# W705A.net
KiCad netlist of a schematic drawn in EAGLE
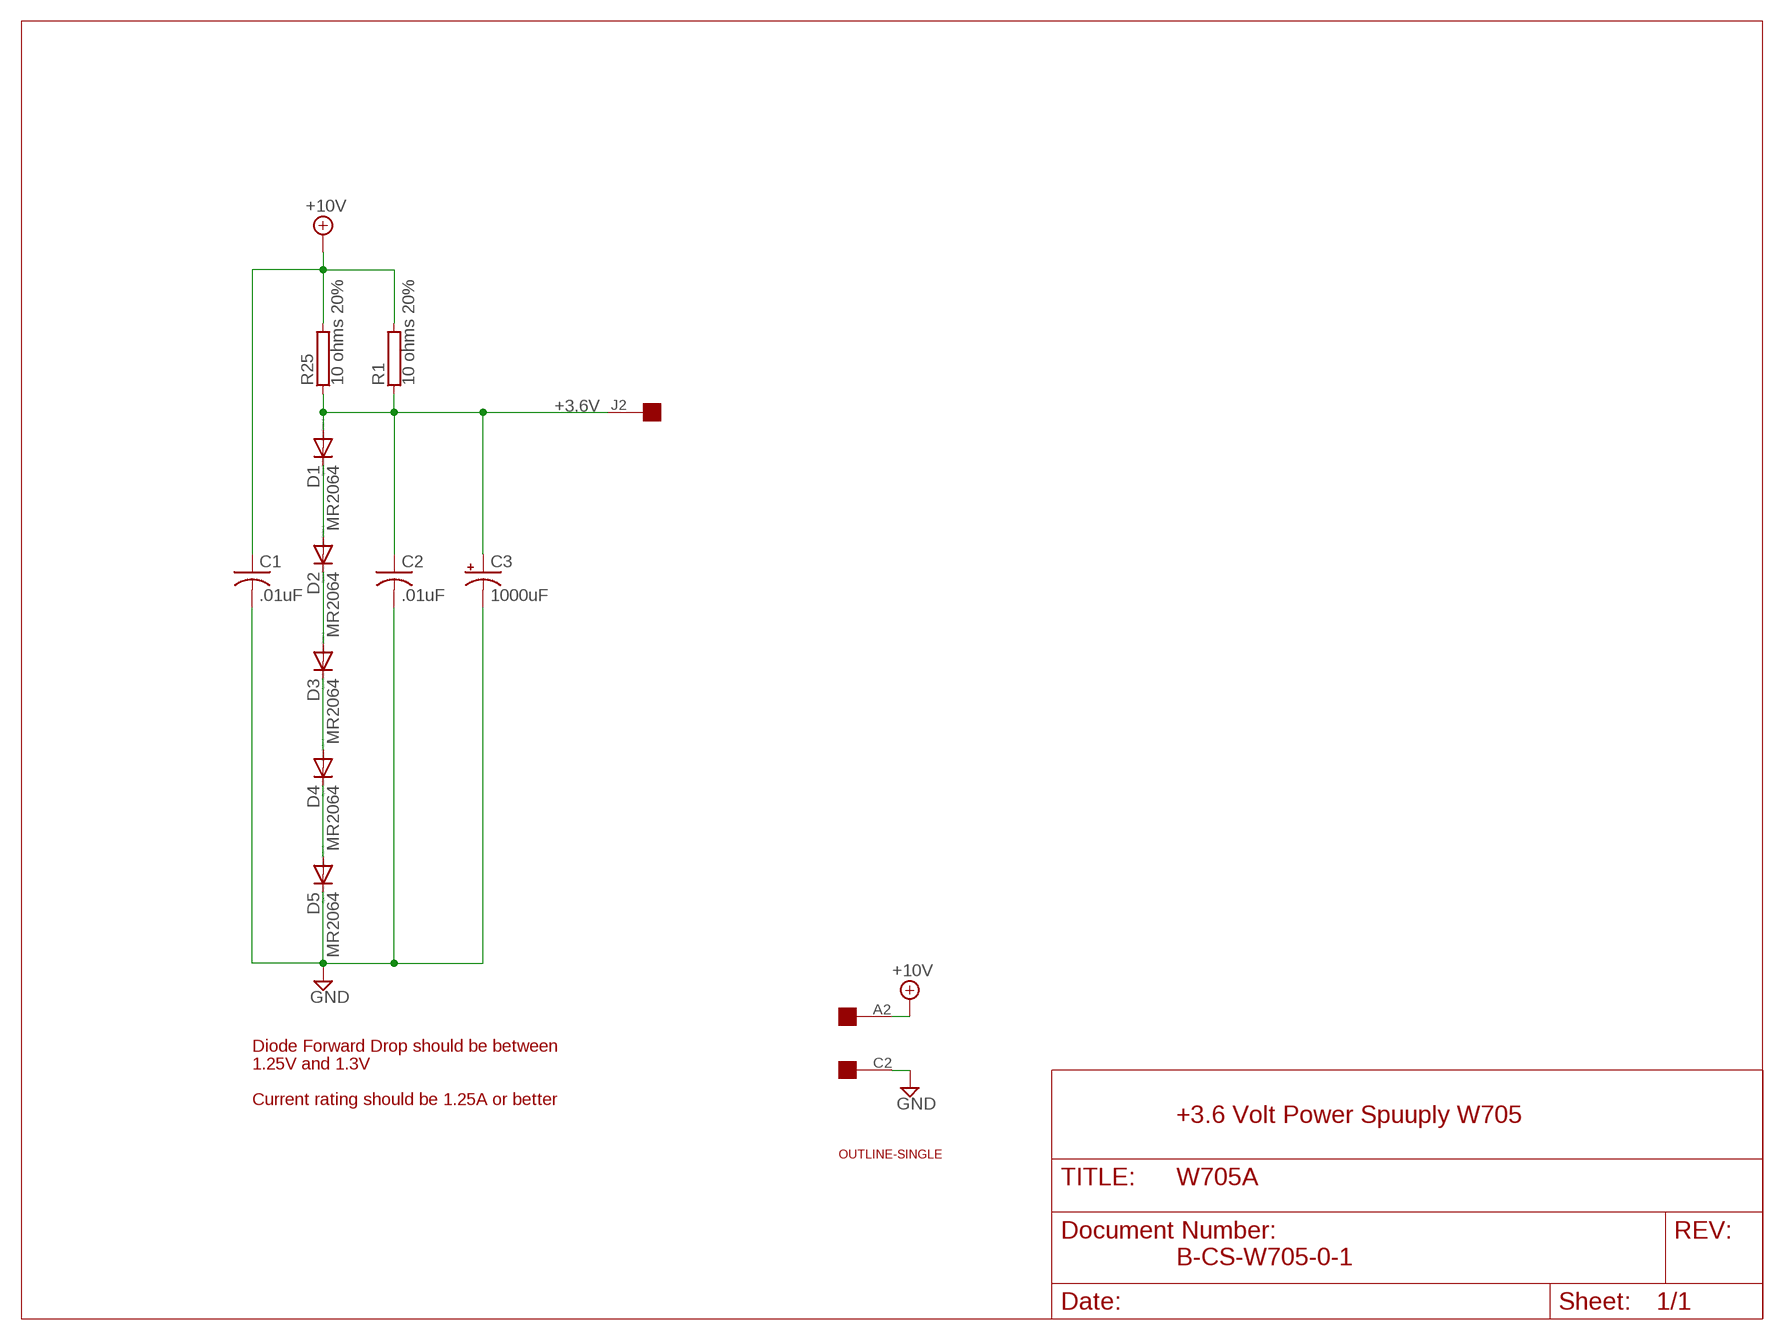
[diagram p0: schematic, sheet 1]

(export (version "E")
  (design (tool "Eeschema 10.0.6"))
  (components
    (comp (ref "C1")
      (value ".01uF")
      (footprint "eagle-import:C050-025X075")
      (libsource (lib "eagle-import") (part "C-US050-025X075"))
    )
    (comp (ref "C2")
      (value ".01uF")
      (footprint "eagle-import:C050-025X075")
      (libsource (lib "eagle-import") (part "C-US050-025X075"))
    )
    (comp (ref "C3")
      (value "1000uF")
      (footprint "eagle-import:E55-25")
      (libsource (lib "eagle-import") (part "CPOL-USE55-25AXIAL"))
    )
    (comp (ref "D1")
      (value "MR2064")
      (footprint "eagle-import:DO41-10")
      (libsource (lib "eagle-import") (part "1N4004"))
    )
    (comp (ref "D2")
      (value "MR2064")
      (footprint "eagle-import:DO41-10")
      (libsource (lib "eagle-import") (part "1N4004"))
    )
    (comp (ref "D3")
      (value "MR2064")
      (footprint "eagle-import:DO41-10")
      (libsource (lib "eagle-import") (part "1N4004"))
    )
    (comp (ref "D4")
      (value "MR2064")
      (footprint "eagle-import:DO41-10")
      (libsource (lib "eagle-import") (part "1N4004"))
    )
    (comp (ref "D5")
      (value "MR2064")
      (footprint "eagle-import:DO41-10")
      (libsource (lib "eagle-import") (part "1N4004"))
    )
    (comp (ref "R1")
      (value "10 ohms 20%")
      (footprint "eagle-import:KH216-8")
      (libsource (lib "eagle-import") (part "RKH216-8"))
    )
    (comp (ref "R25")
      (value "10 ohms 20%")
      (footprint "eagle-import:KH216-8")
      (libsource (lib "eagle-import") (part "RKH216-8"))
    )
    (comp (ref "U$1")
      (value "OUTLINE-SINGLE")
      (footprint "eagle-import:SINGLE")
      (libsource (lib "eagle-import") (part "OUTLINE-SINGLE"))
    )
    (comp (ref "U$2")
      (value "EDGE-1")
      (footprint "eagle-import:EDGE-CON1")
      (libsource (lib "eagle-import") (part "EDGE-1"))
    )
  )
  (nets
    (net (code "1") (name "+10V") (class "Default")
      (node (ref "C1") (pin "1") (pinfunction "1_1") (pintype "passive"))
      (node (ref "R1") (pin "2") (pinfunction "2_2") (pintype "passive"))
      (node (ref "R25") (pin "2") (pinfunction "2_2") (pintype "passive"))
      (node (ref "U$2") (pin "A2") (pinfunction "1_A2") (pintype "bidirectional"))
    )
    (net (code "2") (name "/+3.6V") (class "Default")
      (node (ref "C2") (pin "1") (pinfunction "1_1") (pintype "passive"))
      (node (ref "C3") (pin "+") (pinfunction "+_+") (pintype "passive"))
      (node (ref "D1") (pin "A") (pinfunction "A_A") (pintype "passive"))
      (node (ref "R1") (pin "1") (pinfunction "1_1") (pintype "passive"))
      (node (ref "R25") (pin "1") (pinfunction "1_1") (pintype "passive"))
      (node (ref "U$2") (pin "J2") (pinfunction "1_J2") (pintype "bidirectional"))
    )
    (net (code "3") (name "GND") (class "Default")
      (node (ref "C1") (pin "2") (pinfunction "2_2") (pintype "passive"))
      (node (ref "C2") (pin "2") (pinfunction "2_2") (pintype "passive"))
      (node (ref "C3") (pin "-") (pinfunction "-_-") (pintype "passive"))
      (node (ref "D5") (pin "C") (pinfunction "C_C") (pintype "passive"))
      (node (ref "U$2") (pin "C2") (pinfunction "1_C2") (pintype "bidirectional"))
    )
    (net (code "4") (name "Net-(D1-PadC)") (class "Default")
      (node (ref "D1") (pin "C") (pinfunction "C_C") (pintype "passive"))
      (node (ref "D2") (pin "A") (pinfunction "A_A") (pintype "passive"))
    )
    (net (code "5") (name "Net-(D2-PadC)") (class "Default")
      (node (ref "D2") (pin "C") (pinfunction "C_C") (pintype "passive"))
      (node (ref "D3") (pin "A") (pinfunction "A_A") (pintype "passive"))
    )
    (net (code "6") (name "Net-(D3-PadC)") (class "Default")
      (node (ref "D3") (pin "C") (pinfunction "C_C") (pintype "passive"))
      (node (ref "D4") (pin "A") (pinfunction "A_A") (pintype "passive"))
    )
    (net (code "7") (name "Net-(D4-PadC)") (class "Default")
      (node (ref "D4") (pin "C") (pinfunction "C_C") (pintype "passive"))
      (node (ref "D5") (pin "A") (pinfunction "A_A") (pintype "passive"))
    )
  )
)
